# biolab.net
KiCad netlist of a schematic drawn in Altium Designer
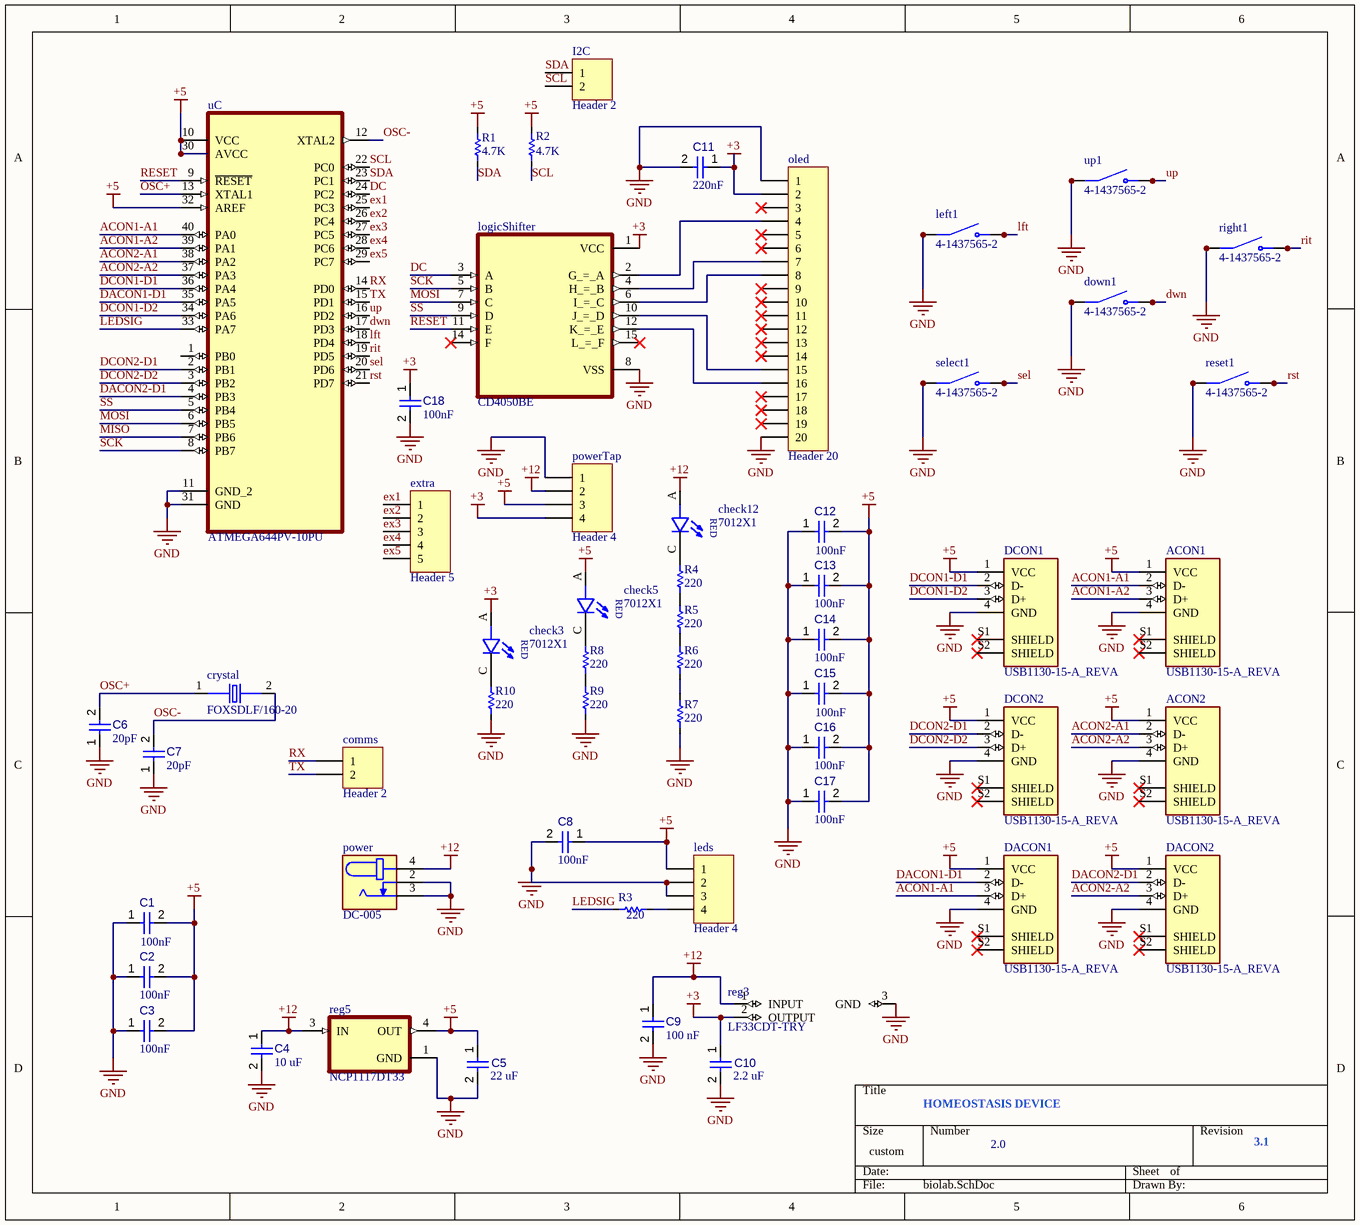
[diagram p0: biolab.SchDoc]

(export (version "E")
  (design (tool "Eeschema 10.0.6"))
  (components
    (comp (ref "ACON1")
      (value "USB1130-15-A_REVA")
      (footprint "GCT_USB1130-15-A_REVA")
      (fields (field (name "MF") "{'manufacturer': u'Global Connector Technology'}"))
      (libsource (lib "SnapEDA_Library") (part "USB1130-15-A_REVA"))
    )
    (comp (ref "ACON2")
      (value "USB1130-15-A_REVA")
      (footprint "GCT_USB1130-15-A_REVA")
      (fields (field (name "MF") "{'manufacturer': u'Global Connector Technology'}"))
      (libsource (lib "SnapEDA_Library") (part "USB1130-15-A_REVA"))
    )
    (comp (ref "C1")
      (value "100nF")
      (footprint "CAPC0805(2012)145_L")
      (description "Chip Capacitor, 4.7µF +/-40%, 25V, 0805, Thickness 1.45 mm")
      (fields (field (name "TOLERANCE") "20%") (field (name "Comment") "Capacitor 4.7µF +/-40% 25V 0805"))
      (libsource (lib "University of Minnesota - Solar Vehicle Project") (part "CAP-NP-2"))
    )
    (comp (ref "C2")
      (value "100nF")
      (footprint "CAPC0805(2012)145_L")
      (description "Chip Capacitor, 4.7µF +/-40%, 25V, 0805, Thickness 1.45 mm")
      (fields (field (name "TOLERANCE") "20%") (field (name "Comment") "Capacitor 4.7µF +/-40% 25V 0805"))
      (libsource (lib "University of Minnesota - Solar Vehicle Project") (part "CAP-NP-2"))
    )
    (comp (ref "C3")
      (value "100nF")
      (footprint "CAPC0805(2012)145_L")
      (description "Chip Capacitor, 4.7µF +/-40%, 25V, 0805, Thickness 1.45 mm")
      (fields (field (name "TOLERANCE") "20%") (field (name "Comment") "Capacitor 4.7µF +/-40% 25V 0805"))
      (libsource (lib "University of Minnesota - Solar Vehicle Project") (part "CAP-NP-2"))
    )
    (comp (ref "C4")
      (value "10 uF")
      (footprint "CAPC0805(2012)145_L")
      (description "Chip Capacitor, 4.7µF +/-40%, 25V, 0805, Thickness 1.45 mm")
      (fields (field (name "TOLERANCE") "20%") (field (name "Comment") "Capacitor 4.7µF +/-40% 25V 0805"))
      (libsource (lib "University of Minnesota - Solar Vehicle Project") (part "CAP-NP-2"))
    )
    (comp (ref "C5")
      (value "22 uF")
      (footprint "CAPC0805(2012)145_L")
      (description "Chip Capacitor, 4.7µF +/-40%, 25V, 0805, Thickness 1.45 mm")
      (fields (field (name "TOLERANCE") "20%") (field (name "Comment") "Capacitor 4.7µF +/-40% 25V 0805"))
      (libsource (lib "University of Minnesota - Solar Vehicle Project") (part "CAP-NP-2"))
    )
    (comp (ref "C6")
      (value "20pF")
      (footprint "CAPC2013X135X45ML10T25")
      (description "Chip Capacitor, 1 uF, +/- 10%, 50 V, 0805 (2012 Metric)")
      (fields (field (name "TOLERANCE") "10%") (field (name "Comment") "Capacitor 1 uF +/- 10% 50 V 0805"))
      (libsource (lib "University of Minnesota - Solar Vehicle Project") (part "CAP-NP-2"))
    )
    (comp (ref "C7")
      (value "20pF")
      (footprint "CAPC2013X135X45ML10T25")
      (description "Chip Capacitor, 1 uF, +/- 10%, 50 V, 0805 (2012 Metric)")
      (fields (field (name "TOLERANCE") "10%") (field (name "Comment") "Capacitor 1 uF +/- 10% 50 V 0805"))
      (libsource (lib "University of Minnesota - Solar Vehicle Project") (part "CAP-NP-2"))
    )
    (comp (ref "C8")
      (value "100nF")
      (footprint "CAPC0805(2012)145_L")
      (description "Chip Capacitor, 4.7µF +/-40%, 25V, 0805, Thickness 1.45 mm")
      (fields (field (name "TOLERANCE") "20%") (field (name "Comment") "Capacitor 4.7µF +/-40% 25V 0805"))
      (libsource (lib "University of Minnesota - Solar Vehicle Project") (part "CAP-NP-2"))
    )
    (comp (ref "C9")
      (value "100 nF")
      (footprint "CAPC0805(2012)145_L")
      (description "Chip Capacitor, 4.7µF +/-40%, 25V, 0805, Thickness 1.45 mm")
      (fields (field (name "TOLERANCE") "20%") (field (name "Comment") "Capacitor 4.7µF +/-40% 25V 0805"))
      (libsource (lib "University of Minnesota - Solar Vehicle Project") (part "CAP-NP-2"))
    )
    (comp (ref "C10")
      (value "2.2 uF")
      (footprint "CAPC0805(2012)145_L")
      (description "Chip Capacitor, 4.7µF +/-40%, 25V, 0805, Thickness 1.45 mm")
      (fields (field (name "TOLERANCE") "20%") (field (name "Comment") "Capacitor 4.7µF +/-40% 25V 0805"))
      (libsource (lib "University of Minnesota - Solar Vehicle Project") (part "CAP-NP-2"))
    )
    (comp (ref "C11")
      (value "220nF")
      (footprint "CAPC0805(2012)145_L")
      (description "Chip Capacitor, 4.7µF +/-40%, 25V, 0805, Thickness 1.45 mm")
      (fields (field (name "TOLERANCE") "20%") (field (name "Comment") "Capacitor 4.7µF +/-40% 25V 0805"))
      (libsource (lib "University of Minnesota - Solar Vehicle Project") (part "CAP-NP-2"))
    )
    (comp (ref "C12")
      (value "100nF")
      (footprint "CAPC0805(2012)145_L")
      (description "Chip Capacitor, 4.7µF +/-40%, 25V, 0805, Thickness 1.45 mm")
      (fields (field (name "TOLERANCE") "20%") (field (name "Comment") "Capacitor 4.7µF +/-40% 25V 0805"))
      (libsource (lib "University of Minnesota - Solar Vehicle Project") (part "CAP-NP-2"))
    )
    (comp (ref "C13")
      (value "100nF")
      (footprint "CAPC0805(2012)145_L")
      (description "Chip Capacitor, 4.7µF +/-40%, 25V, 0805, Thickness 1.45 mm")
      (fields (field (name "TOLERANCE") "20%") (field (name "Comment") "Capacitor 4.7µF +/-40% 25V 0805"))
      (libsource (lib "University of Minnesota - Solar Vehicle Project") (part "CAP-NP-2"))
    )
    (comp (ref "C14")
      (value "100nF")
      (footprint "CAPC0805(2012)145_L")
      (description "Chip Capacitor, 4.7µF +/-40%, 25V, 0805, Thickness 1.45 mm")
      (fields (field (name "TOLERANCE") "20%") (field (name "Comment") "Capacitor 4.7µF +/-40% 25V 0805"))
      (libsource (lib "University of Minnesota - Solar Vehicle Project") (part "CAP-NP-2"))
    )
    (comp (ref "C15")
      (value "100nF")
      (footprint "CAPC0805(2012)145_L")
      (description "Chip Capacitor, 4.7µF +/-40%, 25V, 0805, Thickness 1.45 mm")
      (fields (field (name "TOLERANCE") "20%") (field (name "Comment") "Capacitor 4.7µF +/-40% 25V 0805"))
      (libsource (lib "University of Minnesota - Solar Vehicle Project") (part "CAP-NP-2"))
    )
    (comp (ref "C16")
      (value "100nF")
      (footprint "CAPC0805(2012)145_L")
      (description "Chip Capacitor, 4.7µF +/-40%, 25V, 0805, Thickness 1.45 mm")
      (fields (field (name "TOLERANCE") "20%") (field (name "Comment") "Capacitor 4.7µF +/-40% 25V 0805"))
      (libsource (lib "University of Minnesota - Solar Vehicle Project") (part "CAP-NP-2"))
    )
    (comp (ref "C17")
      (value "100nF")
      (footprint "CAPC0805(2012)145_L")
      (description "Chip Capacitor, 4.7µF +/-40%, 25V, 0805, Thickness 1.45 mm")
      (fields (field (name "TOLERANCE") "20%") (field (name "Comment") "Capacitor 4.7µF +/-40% 25V 0805"))
      (libsource (lib "University of Minnesota - Solar Vehicle Project") (part "CAP-NP-2"))
    )
    (comp (ref "C18")
      (value "100nF")
      (footprint "CAPC0805(2012)145_L")
      (description "Chip Capacitor, 4.7µF +/-40%, 25V, 0805, Thickness 1.45 mm")
      (fields (field (name "TOLERANCE") "20%") (field (name "Comment") "Capacitor 4.7µF +/-40% 25V 0805"))
      (libsource (lib "University of Minnesota - Solar Vehicle Project") (part "CAP-NP-2"))
    )
    (comp (ref "check3")
      (value "7012X1")
      (footprint "LED_7012X1")
      (description "Red LED Indication - Discrete 1.7V 0805 (2012 Metric)")
      (fields (field (name "MF") "{'manufacturer': u'Visual'}"))
      (libsource (lib "SnapEDA_Library") (part "7012X1"))
    )
    (comp (ref "check5")
      (value "7012X1")
      (footprint "LED_7012X1")
      (description "Red LED Indication - Discrete 1.7V 0805 (2012 Metric)")
      (fields (field (name "MF") "{'manufacturer': u'Visual'}"))
      (libsource (lib "SnapEDA_Library") (part "7012X1"))
    )
    (comp (ref "check12")
      (value "7012X1")
      (footprint "LED_7012X1")
      (description "Red LED Indication - Discrete 1.7V 0805 (2012 Metric)")
      (fields (field (name "MF") "{'manufacturer': u'Visual'}"))
      (libsource (lib "SnapEDA_Library") (part "7012X1"))
    )
    (comp (ref "comms")
      (value "Header 2")
      (footprint "HDR1X2")
      (description "Header, 2-Pin")
      (fields (field (name "PUBLISHER") "Altium Limited"))
      (libsource (lib "Miscellaneous Connectors") (part "Header 2"))
    )
    (comp (ref "crystal")
      (value "FOXSDLF/160-20")
      (footprint "XTAL_FOXSDLF/160-20")
      (description "Crystal 16MHz 20pF 2-Pin HC-49/SD")
      (fields (field (name "MF") "{'manufacturer': u'Fox Electronics'}"))
      (libsource (lib "SnapEDA_Library") (part "FOXSDLF/160-20"))
    )
    (comp (ref "DACON1")
      (value "USB1130-15-A_REVA")
      (footprint "GCT_USB1130-15-A_REVA")
      (fields (field (name "MF") "{'manufacturer': u'Global Connector Technology'}"))
      (libsource (lib "SnapEDA_Library") (part "USB1130-15-A_REVA"))
    )
    (comp (ref "DACON2")
      (value "USB1130-15-A_REVA")
      (footprint "GCT_USB1130-15-A_REVA")
      (fields (field (name "MF") "{'manufacturer': u'Global Connector Technology'}"))
      (libsource (lib "SnapEDA_Library") (part "USB1130-15-A_REVA"))
    )
    (comp (ref "DCON1")
      (value "USB1130-15-A_REVA")
      (footprint "GCT_USB1130-15-A_REVA")
      (fields (field (name "MF") "{'manufacturer': u'Global Connector Technology'}"))
      (libsource (lib "SnapEDA_Library") (part "USB1130-15-A_REVA"))
    )
    (comp (ref "DCON2")
      (value "USB1130-15-A_REVA")
      (footprint "GCT_USB1130-15-A_REVA")
      (fields (field (name "MF") "{'manufacturer': u'Global Connector Technology'}"))
      (libsource (lib "SnapEDA_Library") (part "USB1130-15-A_REVA"))
    )
    (comp (ref "down1")
      (value "4-1437565-2")
      (footprint "SW_4-1437565-2")
      (fields (field (name "MF") "{'manufacturer': u'TE Connectivity'}"))
      (libsource (lib "SnapEDA_Library") (part "4-1437565-2"))
    )
    (comp (ref "extra")
      (value "Header 5")
      (footprint "HDR1X5")
      (description "Header, 5-Pin")
      (fields (field (name "PUBLISHER") "Altium Limited"))
      (libsource (lib "Miscellaneous Connectors") (part "Header 5"))
    )
    (comp (ref "I2C")
      (value "Header 2")
      (footprint "HDR1X2")
      (description "Header, 2-Pin")
      (fields (field (name "PUBLISHER") "Altium Limited"))
      (libsource (lib "Miscellaneous Connectors") (part "Header 2"))
    )
    (comp (ref "leds")
      (value "Header 4")
      (footprint "HDR1X4")
      (description "Header, 4-Pin")
      (fields (field (name "PUBLISHER") "Altium Limited"))
      (libsource (lib "Miscellaneous Connectors") (part "Header 4"))
    )
    (comp (ref "left1")
      (value "4-1437565-2")
      (footprint "SW_4-1437565-2")
      (fields (field (name "MF") "{'manufacturer': u'TE Connectivity'}"))
      (libsource (lib "SnapEDA_Library") (part "4-1437565-2"))
    )
    (comp (ref "logicShifter")
      (value "CD4050BE")
      (footprint "DIP794W45P254L1969H508Q16")
      (fields (field (name "MF") "{'manufacturer': u'Texas Instruments'}"))
      (libsource (lib "SnapEDA_Library") (part "CD4050BE"))
    )
    (comp (ref "oled")
      (value "Header 20")
      (footprint "HDR1X20")
      (description "Header, 20-Pin")
      (fields (field (name "PUBLISHER") "Altium Limited"))
      (libsource (lib "Miscellaneous Connectors") (part "Header 20"))
    )
    (comp (ref "power")
      (value "DC-005")
      (footprint "NINIGI_DC-005")
      (description "DC Jack")
      (fields (field (name "MF") "{'manufacturer': u'Best Inc.'}"))
      (libsource (lib "SnapEDA_Library") (part "DC-005"))
    )
    (comp (ref "powerTap")
      (value "Header 4")
      (footprint "HDR1X4")
      (description "Header, 4-Pin")
      (fields (field (name "PUBLISHER") "Altium Limited"))
      (libsource (lib "Miscellaneous Connectors") (part "Header 4"))
    )
    (comp (ref "R1")
      (value "4.7K")
      (footprint "0805_Resistor")
      (description "RES 4.7K OHM 1/8W 1% 0805 SMD")
      (fields
        (field (name "MANUFACTURER") "Yageo")
        (field (name "MANUFACTURER PART NUMBER") "AC0805FR-074K7L")
        (field (name "SVP CREATOR") "Andrew Wu")
      )
      (libsource (lib "University of Minnesota - Solar Vehicle Project") (part "Symbol"))
    )
    (comp (ref "R2")
      (value "4.7K")
      (footprint "0805_Resistor")
      (description "RES 4.7K OHM 1/8W 1% 0805 SMD")
      (fields
        (field (name "MANUFACTURER") "Yageo")
        (field (name "MANUFACTURER PART NUMBER") "AC0805FR-074K7L")
        (field (name "SVP CREATOR") "Andrew Wu")
      )
      (libsource (lib "University of Minnesota - Solar Vehicle Project") (part "Symbol"))
    )
    (comp (ref "R3")
      (value "220")
      (footprint "0805_Resistor")
      (description "RES 4.7K OHM 1/8W 1% 0805 SMD")
      (fields
        (field (name "MANUFACTURER") "Yageo")
        (field (name "MANUFACTURER PART NUMBER") "AC0805FR-074K7L")
        (field (name "SVP CREATOR") "Andrew Wu")
      )
      (libsource (lib "University of Minnesota - Solar Vehicle Project") (part "Symbol"))
    )
    (comp (ref "R4")
      (value "220")
      (footprint "0805_Resistor")
      (description "RES 4.7K OHM 1/8W 1% 0805 SMD")
      (fields
        (field (name "MANUFACTURER") "Yageo")
        (field (name "MANUFACTURER PART NUMBER") "AC0805FR-074K7L")
        (field (name "SVP CREATOR") "Andrew Wu")
      )
      (libsource (lib "University of Minnesota - Solar Vehicle Project") (part "Symbol"))
    )
    (comp (ref "R5")
      (value "220")
      (footprint "0805_Resistor")
      (description "RES 4.7K OHM 1/8W 1% 0805 SMD")
      (fields
        (field (name "MANUFACTURER") "Yageo")
        (field (name "MANUFACTURER PART NUMBER") "AC0805FR-074K7L")
        (field (name "SVP CREATOR") "Andrew Wu")
      )
      (libsource (lib "University of Minnesota - Solar Vehicle Project") (part "Symbol"))
    )
    (comp (ref "R6")
      (value "220")
      (footprint "0805_Resistor")
      (description "RES 4.7K OHM 1/8W 1% 0805 SMD")
      (fields
        (field (name "MANUFACTURER") "Yageo")
        (field (name "MANUFACTURER PART NUMBER") "AC0805FR-074K7L")
        (field (name "SVP CREATOR") "Andrew Wu")
      )
      (libsource (lib "University of Minnesota - Solar Vehicle Project") (part "Symbol"))
    )
    (comp (ref "R7")
      (value "220")
      (footprint "0805_Resistor")
      (description "RES 4.7K OHM 1/8W 1% 0805 SMD")
      (fields
        (field (name "MANUFACTURER") "Yageo")
        (field (name "MANUFACTURER PART NUMBER") "AC0805FR-074K7L")
        (field (name "SVP CREATOR") "Andrew Wu")
      )
      (libsource (lib "University of Minnesota - Solar Vehicle Project") (part "Symbol"))
    )
    (comp (ref "R8")
      (value "220")
      (footprint "0805_Resistor")
      (description "RES 4.7K OHM 1/8W 1% 0805 SMD")
      (fields
        (field (name "MANUFACTURER") "Yageo")
        (field (name "MANUFACTURER PART NUMBER") "AC0805FR-074K7L")
        (field (name "SVP CREATOR") "Andrew Wu")
      )
      (libsource (lib "University of Minnesota - Solar Vehicle Project") (part "Symbol"))
    )
    (comp (ref "R9")
      (value "220")
      (footprint "0805_Resistor")
      (description "RES 4.7K OHM 1/8W 1% 0805 SMD")
      (fields
        (field (name "MANUFACTURER") "Yageo")
        (field (name "MANUFACTURER PART NUMBER") "AC0805FR-074K7L")
        (field (name "SVP CREATOR") "Andrew Wu")
      )
      (libsource (lib "University of Minnesota - Solar Vehicle Project") (part "Symbol"))
    )
    (comp (ref "R10")
      (value "220")
      (footprint "0805_Resistor")
      (description "RES 4.7K OHM 1/8W 1% 0805 SMD")
      (fields
        (field (name "MANUFACTURER") "Yageo")
        (field (name "MANUFACTURER PART NUMBER") "AC0805FR-074K7L")
        (field (name "SVP CREATOR") "Andrew Wu")
      )
      (libsource (lib "University of Minnesota - Solar Vehicle Project") (part "Symbol"))
    )
    (comp (ref "reg3")
      (value "LF33CDT-TRY")
      (footprint "LD1117DT33")
      (fields (field (name "MF") "{'manufacturer': u'STMicroelectronics'}"))
      (libsource (lib "SnapEDA_Library") (part "LF33CDT-TRY"))
    )
    (comp (ref "reg5")
      (value "NCP1117DT33")
      (footprint "VREG_NCP1117DT33")
      (description "1.0 A Positive LDO Linear Voltage Regulator (Fixed and Adjustable) Vout: 3.3 V")
      (fields (field (name "MF") "{'manufacturer': u'ON Semiconductor'}"))
      (libsource (lib "SnapEDA_Library") (part "NCP1117DT33"))
    )
    (comp (ref "reset1")
      (value "4-1437565-2")
      (footprint "SW_4-1437565-2")
      (fields (field (name "MF") "{'manufacturer': u'TE Connectivity'}"))
      (libsource (lib "SnapEDA_Library") (part "4-1437565-2"))
    )
    (comp (ref "right1")
      (value "4-1437565-2")
      (footprint "SW_4-1437565-2")
      (fields (field (name "MF") "{'manufacturer': u'TE Connectivity'}"))
      (libsource (lib "SnapEDA_Library") (part "4-1437565-2"))
    )
    (comp (ref "select1")
      (value "4-1437565-2")
      (footprint "SW_4-1437565-2")
      (fields (field (name "MF") "{'manufacturer': u'TE Connectivity'}"))
      (libsource (lib "SnapEDA_Library") (part "4-1437565-2"))
    )
    (comp (ref "uC")
      (value "ATMEGA644PV-10PU")
      (footprint "DIP254P1524X483-40")
      (description "8-bit Microcontroller with In-System Programmable  Flash")
      (fields (field (name "MF") "{'manufacturer': u'Microchip Technology'}"))
      (libsource (lib "SnapEDA_Library") (part "ATMEGA644PV-10PU"))
    )
    (comp (ref "up1")
      (value "4-1437565-2")
      (footprint "SW_4-1437565-2")
      (fields (field (name "MF") "{'manufacturer': u'TE Connectivity'}"))
      (libsource (lib "SnapEDA_Library") (part "4-1437565-2"))
    )
  )
  (nets
    (net (code "1") (name "+3") (class "Default")
      (node (ref "C10") (pin "1") (pinfunction "1_1") (pintype "passive"))
      (node (ref "C11") (pin "1") (pinfunction "1_1") (pintype "passive"))
      (node (ref "C18") (pin "1") (pinfunction "1_1") (pintype "passive"))
      (node (ref "check3") (pin "A") (pinfunction "A_A") (pintype "passive"))
      (node (ref "logicShifter") (pin "1") (pinfunction "VCC_1") (pintype "power_in"))
      (node (ref "oled") (pin "2") (pinfunction "2_2") (pintype "passive"))
      (node (ref "powerTap") (pin "4") (pinfunction "4_4") (pintype "passive"))
      (node (ref "reg3") (pin "2") (pinfunction "OUTPUT_2") (pintype "bidirectional"))
    )
    (net (code "2") (name "+5") (class "Default")
      (node (ref "ACON1") (pin "1") (pinfunction "VCC_1") (pintype "power_in"))
      (node (ref "ACON2") (pin "1") (pinfunction "VCC_1") (pintype "power_in"))
      (node (ref "C1") (pin "2") (pinfunction "2_2") (pintype "passive"))
      (node (ref "C12") (pin "2") (pinfunction "2_2") (pintype "passive"))
      (node (ref "C13") (pin "2") (pinfunction "2_2") (pintype "passive"))
      (node (ref "C14") (pin "2") (pinfunction "2_2") (pintype "passive"))
      (node (ref "C15") (pin "2") (pinfunction "2_2") (pintype "passive"))
      (node (ref "C16") (pin "2") (pinfunction "2_2") (pintype "passive"))
      (node (ref "C17") (pin "2") (pinfunction "2_2") (pintype "passive"))
      (node (ref "C2") (pin "2") (pinfunction "2_2") (pintype "passive"))
      (node (ref "C3") (pin "2") (pinfunction "2_2") (pintype "passive"))
      (node (ref "C5") (pin "1") (pinfunction "1_1") (pintype "passive"))
      (node (ref "C8") (pin "1") (pinfunction "1_1") (pintype "passive"))
      (node (ref "DACON1") (pin "1") (pinfunction "VCC_1") (pintype "power_in"))
      (node (ref "DACON2") (pin "1") (pinfunction "VCC_1") (pintype "power_in"))
      (node (ref "DCON1") (pin "1") (pinfunction "VCC_1") (pintype "power_in"))
      (node (ref "DCON2") (pin "1") (pinfunction "VCC_1") (pintype "power_in"))
      (node (ref "R1") (pin "1") (pinfunction "1_1") (pintype "passive"))
      (node (ref "R2") (pin "1") (pinfunction "1_1") (pintype "passive"))
      (node (ref "check5") (pin "A") (pinfunction "A_A") (pintype "passive"))
      (node (ref "leds") (pin "1") (pinfunction "1_1") (pintype "passive"))
      (node (ref "powerTap") (pin "3") (pinfunction "3_3") (pintype "passive"))
      (node (ref "reg5") (pin "4") (pinfunction "OUT_4") (pintype "output"))
      (node (ref "uC") (pin "10") (pinfunction "VCC_10") (pintype "power_in"))
      (node (ref "uC") (pin "30") (pinfunction "AVCC_30") (pintype "power_in"))
      (node (ref "uC") (pin "32") (pinfunction "AREF_32") (pintype "input"))
    )
    (net (code "3") (name "+12") (class "Default")
      (node (ref "C4") (pin "1") (pinfunction "1_1") (pintype "passive"))
      (node (ref "C9") (pin "1") (pinfunction "1_1") (pintype "passive"))
      (node (ref "check12") (pin "A") (pinfunction "A_A") (pintype "passive"))
      (node (ref "power") (pin "4") (pinfunction "2_4") (pintype "passive"))
      (node (ref "powerTap") (pin "2") (pinfunction "2_2") (pintype "passive"))
      (node (ref "reg3") (pin "1") (pinfunction "INPUT_1") (pintype "bidirectional"))
      (node (ref "reg5") (pin "3") (pinfunction "IN_3") (pintype "input"))
    )
    (net (code "4") (name "/ACON1-A1") (class "Default")
      (node (ref "ACON1") (pin "2") (pinfunction "D-_2") (pintype "bidirectional"))
      (node (ref "DACON1") (pin "3") (pinfunction "D+_3") (pintype "bidirectional"))
      (node (ref "uC") (pin "40") (pinfunction "PA0_40") (pintype "bidirectional"))
    )
    (net (code "5") (name "/ACON1-A2") (class "Default")
      (node (ref "ACON1") (pin "3") (pinfunction "D+_3") (pintype "bidirectional"))
      (node (ref "uC") (pin "39") (pinfunction "PA1_39") (pintype "bidirectional"))
    )
    (net (code "6") (name "/ACON2-A1") (class "Default")
      (node (ref "ACON2") (pin "2") (pinfunction "D-_2") (pintype "bidirectional"))
      (node (ref "uC") (pin "38") (pinfunction "PA2_38") (pintype "bidirectional"))
    )
    (net (code "7") (name "/ACON2-A2") (class "Default")
      (node (ref "ACON2") (pin "3") (pinfunction "D+_3") (pintype "bidirectional"))
      (node (ref "DACON2") (pin "3") (pinfunction "D+_3") (pintype "bidirectional"))
      (node (ref "uC") (pin "37") (pinfunction "PA3_37") (pintype "bidirectional"))
    )
    (net (code "8") (name "/DACON1-D1") (class "Default")
      (node (ref "DACON1") (pin "2") (pinfunction "D-_2") (pintype "bidirectional"))
      (node (ref "uC") (pin "35") (pinfunction "PA5_35") (pintype "bidirectional"))
    )
    (net (code "9") (name "/DACON2-D1") (class "Default")
      (node (ref "DACON2") (pin "2") (pinfunction "D-_2") (pintype "bidirectional"))
      (node (ref "uC") (pin "4") (pinfunction "PB3_4") (pintype "bidirectional"))
    )
    (net (code "10") (name "/DC") (class "Default")
      (node (ref "logicShifter") (pin "3") (pinfunction "A_3") (pintype "input"))
      (node (ref "uC") (pin "24") (pinfunction "PC2_24") (pintype "bidirectional"))
    )
    (net (code "11") (name "/DCON1-D1") (class "Default")
      (node (ref "DCON1") (pin "2") (pinfunction "D-_2") (pintype "bidirectional"))
      (node (ref "uC") (pin "36") (pinfunction "PA4_36") (pintype "bidirectional"))
    )
    (net (code "12") (name "/DCON1-D2") (class "Default")
      (node (ref "DCON1") (pin "3") (pinfunction "D+_3") (pintype "bidirectional"))
      (node (ref "uC") (pin "34") (pinfunction "PA6_34") (pintype "bidirectional"))
    )
    (net (code "13") (name "/DCON2-D1") (class "Default")
      (node (ref "DCON2") (pin "2") (pinfunction "D-_2") (pintype "bidirectional"))
      (node (ref "uC") (pin "2") (pinfunction "PB1_2") (pintype "bidirectional"))
    )
    (net (code "14") (name "/DCON2-D2") (class "Default")
      (node (ref "DCON2") (pin "3") (pinfunction "D+_3") (pintype "bidirectional"))
      (node (ref "uC") (pin "3") (pinfunction "PB2_3") (pintype "bidirectional"))
    )
    (net (code "15") (name "/LEDSIG") (class "Default")
      (node (ref "R3") (pin "1") (pinfunction "1_1") (pintype "passive"))
      (node (ref "uC") (pin "33") (pinfunction "PA7_33") (pintype "bidirectional"))
    )
    (net (code "16") (name "/MISO") (class "Default")
      (node (ref "uC") (pin "7") (pinfunction "PB6_7") (pintype "bidirectional"))
    )
    (net (code "17") (name "/MOSI") (class "Default")
      (node (ref "logicShifter") (pin "7") (pinfunction "C_7") (pintype "input"))
      (node (ref "uC") (pin "6") (pinfunction "PB5_6") (pintype "bidirectional"))
    )
    (net (code "18") (name "/OSC+") (class "Default")
      (node (ref "C6") (pin "2") (pinfunction "2_2") (pintype "passive"))
      (node (ref "crystal") (pin "1") (pinfunction "1_1") (pintype "passive"))
      (node (ref "uC") (pin "13") (pinfunction "XTAL1_13") (pintype "input"))
    )
    (net (code "19") (name "/OSC-") (class "Default")
      (node (ref "C7") (pin "2") (pinfunction "2_2") (pintype "passive"))
      (node (ref "crystal") (pin "2") (pinfunction "2_2") (pintype "passive"))
      (node (ref "uC") (pin "12") (pinfunction "XTAL2_12") (pintype "output"))
    )
    (net (code "20") (name "/RESET") (class "Default")
      (node (ref "logicShifter") (pin "11") (pinfunction "E_11") (pintype "input"))
      (node (ref "uC") (pin "9") (pinfunction "~{RESET}_9") (pintype "input"))
    )
    (net (code "21") (name "/RX") (class "Default")
      (node (ref "comms") (pin "1") (pinfunction "1_1") (pintype "passive"))
      (node (ref "uC") (pin "14") (pinfunction "PD0_14") (pintype "bidirectional"))
    )
    (net (code "22") (name "/SCK") (class "Default")
      (node (ref "logicShifter") (pin "5") (pinfunction "B_5") (pintype "input"))
      (node (ref "uC") (pin "8") (pinfunction "PB7_8") (pintype "bidirectional"))
    )
    (net (code "23") (name "/SCL") (class "Default")
      (node (ref "I2C") (pin "2") (pinfunction "2_2") (pintype "passive"))
      (node (ref "R2") (pin "2") (pinfunction "2_2") (pintype "passive"))
      (node (ref "uC") (pin "22") (pinfunction "PC0_22") (pintype "bidirectional"))
    )
    (net (code "24") (name "/SDA") (class "Default")
      (node (ref "I2C") (pin "1") (pinfunction "1_1") (pintype "passive"))
      (node (ref "R1") (pin "2") (pinfunction "2_2") (pintype "passive"))
      (node (ref "uC") (pin "23") (pinfunction "PC1_23") (pintype "bidirectional"))
    )
    (net (code "25") (name "/SS") (class "Default")
      (node (ref "logicShifter") (pin "9") (pinfunction "D_9") (pintype "input"))
      (node (ref "uC") (pin "5") (pinfunction "PB4_5") (pintype "bidirectional"))
    )
    (net (code "26") (name "/TX") (class "Default")
      (node (ref "comms") (pin "2") (pinfunction "2_2") (pintype "passive"))
      (node (ref "uC") (pin "15") (pinfunction "PD1_15") (pintype "bidirectional"))
    )
    (net (code "27") (name "/dwn") (class "Default")
      (node (ref "down1") (pin "3") (pinfunction "NO_3") (pintype "passive"))
      (node (ref "down1") (pin "4") (pinfunction "NO_4") (pintype "passive"))
      (node (ref "uC") (pin "17") (pinfunction "PD3_17") (pintype "bidirectional"))
    )
    (net (code "28") (name "/ex1") (class "Default")
      (node (ref "extra") (pin "1") (pinfunction "1_1") (pintype "passive"))
      (node (ref "uC") (pin "25") (pinfunction "PC3_25") (pintype "bidirectional"))
    )
    (net (code "29") (name "/ex2") (class "Default")
      (node (ref "extra") (pin "2") (pinfunction "2_2") (pintype "passive"))
      (node (ref "uC") (pin "26") (pinfunction "PC4_26") (pintype "bidirectional"))
    )
    (net (code "30") (name "/ex3") (class "Default")
      (node (ref "extra") (pin "3") (pinfunction "3_3") (pintype "passive"))
      (node (ref "uC") (pin "27") (pinfunction "PC5_27") (pintype "bidirectional"))
    )
    (net (code "31") (name "/ex4") (class "Default")
      (node (ref "extra") (pin "4") (pinfunction "4_4") (pintype "passive"))
      (node (ref "uC") (pin "28") (pinfunction "PC6_28") (pintype "bidirectional"))
    )
    (net (code "32") (name "/ex5") (class "Default")
      (node (ref "extra") (pin "5") (pinfunction "5_5") (pintype "passive"))
      (node (ref "uC") (pin "29") (pinfunction "PC7_29") (pintype "bidirectional"))
    )
    (net (code "33") (name "/lft") (class "Default")
      (node (ref "left1") (pin "3") (pinfunction "NO_3") (pintype "passive"))
      (node (ref "left1") (pin "4") (pinfunction "NO_4") (pintype "passive"))
      (node (ref "uC") (pin "18") (pinfunction "PD4_18") (pintype "bidirectional"))
    )
    (net (code "34") (name "/rit") (class "Default")
      (node (ref "right1") (pin "3") (pinfunction "NO_3") (pintype "passive"))
      (node (ref "right1") (pin "4") (pinfunction "NO_4") (pintype "passive"))
      (node (ref "uC") (pin "19") (pinfunction "PD5_19") (pintype "bidirectional"))
    )
    (net (code "35") (name "/rst") (class "Default")
      (node (ref "reset1") (pin "3") (pinfunction "NO_3") (pintype "passive"))
      (node (ref "reset1") (pin "4") (pinfunction "NO_4") (pintype "passive"))
      (node (ref "uC") (pin "21") (pinfunction "PD7_21") (pintype "bidirectional"))
    )
    (net (code "36") (name "/sel") (class "Default")
      (node (ref "select1") (pin "3") (pinfunction "NO_3") (pintype "passive"))
      (node (ref "select1") (pin "4") (pinfunction "NO_4") (pintype "passive"))
      (node (ref "uC") (pin "20") (pinfunction "PD6_20") (pintype "bidirectional"))
    )
    (net (code "37") (name "/up") (class "Default")
      (node (ref "uC") (pin "16") (pinfunction "PD2_16") (pintype "bidirectional"))
      (node (ref "up1") (pin "3") (pinfunction "NO_3") (pintype "passive"))
      (node (ref "up1") (pin "4") (pinfunction "NO_4") (pintype "passive"))
    )
    (net (code "38") (name "GND") (class "Default")
      (node (ref "ACON1") (pin "4") (pinfunction "GND_4") (pintype "power_in"))
      (node (ref "ACON2") (pin "4") (pinfunction "GND_4") (pintype "power_in"))
      (node (ref "C1") (pin "1") (pinfunction "1_1") (pintype "passive"))
      (node (ref "C10") (pin "2") (pinfunction "2_2") (pintype "passive"))
      (node (ref "C11") (pin "2") (pinfunction "2_2") (pintype "passive"))
      (node (ref "C12") (pin "1") (pinfunction "1_1") (pintype "passive"))
      (node (ref "C13") (pin "1") (pinfunction "1_1") (pintype "passive"))
      (node (ref "C14") (pin "1") (pinfunction "1_1") (pintype "passive"))
      (node (ref "C15") (pin "1") (pinfunction "1_1") (pintype "passive"))
      (node (ref "C16") (pin "1") (pinfunction "1_1") (pintype "passive"))
      (node (ref "C17") (pin "1") (pinfunction "1_1") (pintype "passive"))
      (node (ref "C18") (pin "2") (pinfunction "2_2") (pintype "passive"))
      (node (ref "C2") (pin "1") (pinfunction "1_1") (pintype "passive"))
      (node (ref "C3") (pin "1") (pinfunction "1_1") (pintype "passive"))
      (node (ref "C4") (pin "2") (pinfunction "2_2") (pintype "passive"))
      (node (ref "C5") (pin "2") (pinfunction "2_2") (pintype "passive"))
      (node (ref "C6") (pin "1") (pinfunction "1_1") (pintype "passive"))
      (node (ref "C7") (pin "1") (pinfunction "1_1") (pintype "passive"))
      (node (ref "C8") (pin "2") (pinfunction "2_2") (pintype "passive"))
      (node (ref "C9") (pin "2") (pinfunction "2_2") (pintype "passive"))
      (node (ref "DACON1") (pin "4") (pinfunction "GND_4") (pintype "power_in"))
      (node (ref "DACON2") (pin "4") (pinfunction "GND_4") (pintype "power_in"))
      (node (ref "DCON1") (pin "4") (pinfunction "GND_4") (pintype "power_in"))
      (node (ref "DCON2") (pin "4") (pinfunction "GND_4") (pintype "power_in"))
      (node (ref "R10") (pin "1") (pinfunction "1_1") (pintype "passive"))
      (node (ref "R7") (pin "1") (pinfunction "1_1") (pintype "passive"))
      (node (ref "R9") (pin "1") (pinfunction "1_1") (pintype "passive"))
      (node (ref "down1") (pin "1") (pinfunction "COM_1") (pintype "passive"))
      (node (ref "down1") (pin "2") (pinfunction "COM_2") (pintype "passive"))
      (node (ref "leds") (pin "2") (pinfunction "2_2") (pintype "passive"))
      (node (ref "leds") (pin "3") (pinfunction "3_3") (pintype "passive"))
      (node (ref "left1") (pin "1") (pinfunction "COM_1") (pintype "passive"))
      (node (ref "left1") (pin "2") (pinfunction "COM_2") (pintype "passive"))
      (node (ref "logicShifter") (pin "8") (pinfunction "VSS_8") (pintype "power_in"))
      (node (ref "oled") (pin "1") (pinfunction "1_1") (pintype "passive"))
      (node (ref "oled") (pin "20") (pinfunction "20_20") (pintype "passive"))
      (node (ref "power") (pin "2") (pinfunction "4_2") (pintype "passive"))
      (node (ref "power") (pin "3") (pinfunction "5_3") (pintype "passive"))
      (node (ref "powerTap") (pin "1") (pinfunction "1_1") (pintype "passive"))
      (node (ref "reg3") (pin "3") (pinfunction "GND_3") (pintype "bidirectional"))
      (node (ref "reg5") (pin "1") (pinfunction "GND_1") (pintype "power_in"))
      (node (ref "reset1") (pin "1") (pinfunction "COM_1") (pintype "passive"))
      (node (ref "reset1") (pin "2") (pinfunction "COM_2") (pintype "passive"))
      (node (ref "right1") (pin "1") (pinfunction "COM_1") (pintype "passive"))
      (node (ref "right1") (pin "2") (pinfunction "COM_2") (pintype "passive"))
      (node (ref "select1") (pin "1") (pinfunction "COM_1") (pintype "passive"))
      (node (ref "select1") (pin "2") (pinfunction "COM_2") (pintype "passive"))
      (node (ref "uC") (pin "11") (pinfunction "GND_2_11") (pintype "passive"))
      (node (ref "uC") (pin "31") (pinfunction "GND_31") (pintype "passive"))
      (node (ref "up1") (pin "1") (pinfunction "COM_1") (pintype "passive"))
      (node (ref "up1") (pin "2") (pinfunction "COM_2") (pintype "passive"))
    )
    (net (code "39") (name "Net-(R3-Pad2)") (class "Default")
      (node (ref "R3") (pin "2") (pinfunction "2_2") (pintype "passive"))
      (node (ref "leds") (pin "4") (pinfunction "4_4") (pintype "passive"))
    )
    (net (code "40") (name "Net-(R4-Pad1)") (class "Default")
      (node (ref "R4") (pin "1") (pinfunction "1_1") (pintype "passive"))
      (node (ref "R5") (pin "2") (pinfunction "2_2") (pintype "passive"))
    )
    (net (code "41") (name "Net-(R4-Pad2)") (class "Default")
      (node (ref "R4") (pin "2") (pinfunction "2_2") (pintype "passive"))
      (node (ref "check12") (pin "C") (pinfunction "C_C") (pintype "passive"))
    )
    (net (code "42") (name "Net-(R5-Pad1)") (class "Default")
      (node (ref "R5") (pin "1") (pinfunction "1_1") (pintype "passive"))
      (node (ref "R6") (pin "2") (pinfunction "2_2") (pintype "passive"))
    )
    (net (code "43") (name "Net-(R6-Pad1)") (class "Default")
      (node (ref "R6") (pin "1") (pinfunction "1_1") (pintype "passive"))
      (node (ref "R7") (pin "2") (pinfunction "2_2") (pintype "passive"))
    )
    (net (code "44") (name "Net-(R8-Pad1)") (class "Default")
      (node (ref "R8") (pin "1") (pinfunction "1_1") (pintype "passive"))
      (node (ref "R9") (pin "2") (pinfunction "2_2") (pintype "passive"))
    )
    (net (code "45") (name "Net-(R8-Pad2)") (class "Default")
      (node (ref "R8") (pin "2") (pinfunction "2_2") (pintype "passive"))
      (node (ref "check5") (pin "C") (pinfunction "C_C") (pintype "passive"))
    )
    (net (code "46") (name "Net-(R10-Pad2)") (class "Default")
      (node (ref "R10") (pin "2") (pinfunction "2_2") (pintype "passive"))
      (node (ref "check3") (pin "C") (pinfunction "C_C") (pintype "passive"))
    )
    (net (code "47") (name "Net-(logicShifter-G_=_A)") (class "Default")
      (node (ref "logicShifter") (pin "2") (pinfunction "G_=_A_2") (pintype "output"))
      (node (ref "oled") (pin "4") (pinfunction "4_4") (pintype "passive"))
    )
    (net (code "48") (name "Net-(logicShifter-H_=_B)") (class "Default")
      (node (ref "logicShifter") (pin "4") (pinfunction "H_=_B_4") (pintype "output"))
      (node (ref "oled") (pin "7") (pinfunction "7_7") (pintype "passive"))
    )
    (net (code "49") (name "Net-(logicShifter-I_=_C)") (class "Default")
      (node (ref "logicShifter") (pin "6") (pinfunction "I_=_C_6") (pintype "output"))
      (node (ref "oled") (pin "8") (pinfunction "8_8") (pintype "passive"))
    )
    (net (code "50") (name "Net-(logicShifter-J_=_D)") (class "Default")
      (node (ref "logicShifter") (pin "10") (pinfunction "J_=_D_10") (pintype "output"))
      (node (ref "oled") (pin "15") (pinfunction "15_15") (pintype "passive"))
    )
    (net (code "51") (name "Net-(logicShifter-K_=_E)") (class "Default")
      (node (ref "logicShifter") (pin "12") (pinfunction "K_=_E_12") (pintype "output"))
      (node (ref "oled") (pin "16") (pinfunction "16_16") (pintype "passive"))
    )
    (net (code "52") (name "unconnected-(ACON1-SHIELD-PadS1)") (class "Default")
      (node (ref "ACON1") (pin "S1") (pinfunction "SHIELD_S1") (pintype "passive+no_connect"))
    )
    (net (code "53") (name "unconnected-(ACON1-SHIELD-PadS2)") (class "Default")
      (node (ref "ACON1") (pin "S2") (pinfunction "SHIELD_S2") (pintype "passive+no_connect"))
    )
    (net (code "54") (name "unconnected-(ACON2-SHIELD-PadS1)") (class "Default")
      (node (ref "ACON2") (pin "S1") (pinfunction "SHIELD_S1") (pintype "passive+no_connect"))
    )
    (net (code "55") (name "unconnected-(ACON2-SHIELD-PadS2)") (class "Default")
      (node (ref "ACON2") (pin "S2") (pinfunction "SHIELD_S2") (pintype "passive+no_connect"))
    )
    (net (code "56") (name "unconnected-(DACON1-SHIELD-PadS1)") (class "Default")
      (node (ref "DACON1") (pin "S1") (pinfunction "SHIELD_S1") (pintype "passive+no_connect"))
    )
    (net (code "57") (name "unconnected-(DACON1-SHIELD-PadS2)") (class "Default")
      (node (ref "DACON1") (pin "S2") (pinfunction "SHIELD_S2") (pintype "passive+no_connect"))
    )
    (net (code "58") (name "unconnected-(DACON2-SHIELD-PadS1)") (class "Default")
      (node (ref "DACON2") (pin "S1") (pinfunction "SHIELD_S1") (pintype "passive+no_connect"))
    )
    (net (code "59") (name "unconnected-(DACON2-SHIELD-PadS2)") (class "Default")
      (node (ref "DACON2") (pin "S2") (pinfunction "SHIELD_S2") (pintype "passive+no_connect"))
    )
    (net (code "60") (name "unconnected-(DCON1-SHIELD-PadS1)") (class "Default")
      (node (ref "DCON1") (pin "S1") (pinfunction "SHIELD_S1") (pintype "passive+no_connect"))
    )
    (net (code "61") (name "unconnected-(DCON1-SHIELD-PadS2)") (class "Default")
      (node (ref "DCON1") (pin "S2") (pinfunction "SHIELD_S2") (pintype "passive+no_connect"))
    )
    (net (code "62") (name "unconnected-(DCON2-SHIELD-PadS1)") (class "Default")
      (node (ref "DCON2") (pin "S1") (pinfunction "SHIELD_S1") (pintype "passive+no_connect"))
    )
    (net (code "63") (name "unconnected-(DCON2-SHIELD-PadS2)") (class "Default")
      (node (ref "DCON2") (pin "S2") (pinfunction "SHIELD_S2") (pintype "passive+no_connect"))
    )
    (net (code "64") (name "unconnected-(logicShifter-F-Pad14)") (class "Default")
      (node (ref "logicShifter") (pin "14") (pinfunction "F_14") (pintype "input+no_connect"))
    )
    (net (code "65") (name "unconnected-(logicShifter-L_=_F-Pad15)") (class "Default")
      (node (ref "logicShifter") (pin "15") (pinfunction "L_=_F_15") (pintype "output+no_connect"))
    )
    (net (code "66") (name "unconnected-(oled-Pad3)") (class "Default")
      (node (ref "oled") (pin "3") (pinfunction "3_3") (pintype "passive+no_connect"))
    )
    (net (code "67") (name "unconnected-(oled-Pad5)") (class "Default")
      (node (ref "oled") (pin "5") (pinfunction "5_5") (pintype "passive+no_connect"))
    )
    (net (code "68") (name "unconnected-(oled-Pad6)") (class "Default")
      (node (ref "oled") (pin "6") (pinfunction "6_6") (pintype "passive+no_connect"))
    )
    (net (code "69") (name "unconnected-(oled-Pad9)") (class "Default")
      (node (ref "oled") (pin "9") (pinfunction "9_9") (pintype "passive+no_connect"))
    )
    (net (code "70") (name "unconnected-(oled-Pad10)") (class "Default")
      (node (ref "oled") (pin "10") (pinfunction "10_10") (pintype "passive+no_connect"))
    )
    (net (code "71") (name "unconnected-(oled-Pad11)") (class "Default")
      (node (ref "oled") (pin "11") (pinfunction "11_11") (pintype "passive+no_connect"))
    )
    (net (code "72") (name "unconnected-(oled-Pad12)") (class "Default")
      (node (ref "oled") (pin "12") (pinfunction "12_12") (pintype "passive+no_connect"))
    )
    (net (code "73") (name "unconnected-(oled-Pad13)") (class "Default")
      (node (ref "oled") (pin "13") (pinfunction "13_13") (pintype "passive+no_connect"))
    )
    (net (code "74") (name "unconnected-(oled-Pad14)") (class "Default")
      (node (ref "oled") (pin "14") (pinfunction "14_14") (pintype "passive+no_connect"))
    )
    (net (code "75") (name "unconnected-(oled-Pad17)") (class "Default")
      (node (ref "oled") (pin "17") (pinfunction "17_17") (pintype "passive+no_connect"))
    )
    (net (code "76") (name "unconnected-(oled-Pad18)") (class "Default")
      (node (ref "oled") (pin "18") (pinfunction "18_18") (pintype "passive+no_connect"))
    )
    (net (code "77") (name "unconnected-(oled-Pad19)") (class "Default")
      (node (ref "oled") (pin "19") (pinfunction "19_19") (pintype "passive+no_connect"))
    )
    (net (code "78") (name "unconnected-(uC-PB0-Pad1)") (class "Default")
      (node (ref "uC") (pin "1") (pinfunction "PB0_1") (pintype "bidirectional"))
    )
  )
)
